# DRV8825_SHIELD_V3.net
KiCad netlist of a schematic drawn in EAGLE
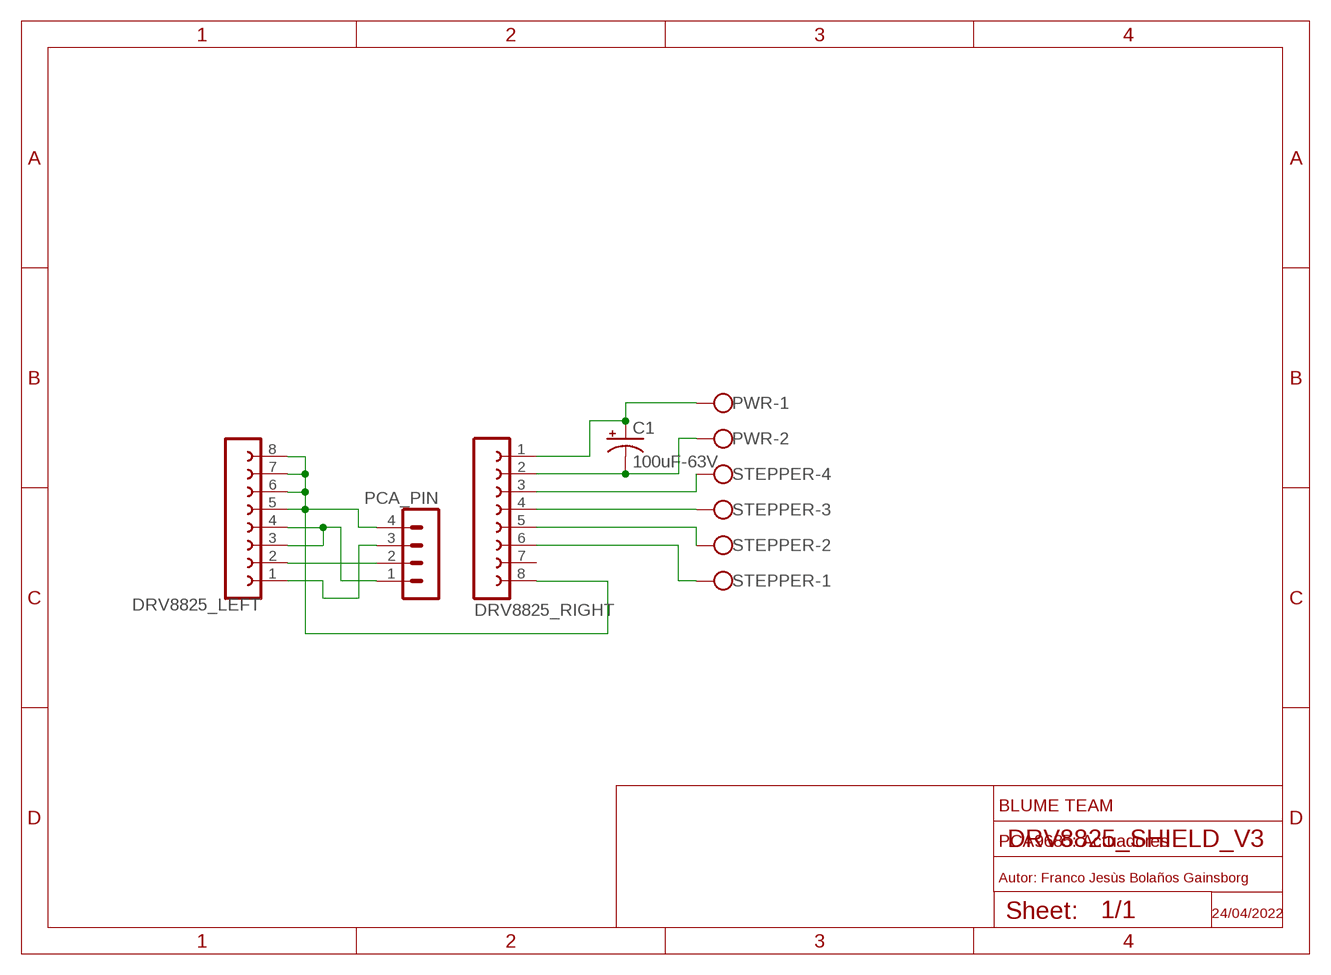
[diagram p0: schematic, sheet 1]

(export (version "E")
  (design (tool "Eeschema 10.0.6"))
  (components
    (comp (ref "C1")
      (value "100uF-63V")
      (footprint "eagle-import:E5-10,5")
      (libsource (lib "eagle-import") (part "CPOL-USE5-10.5"))
    )
    (comp (ref "DRV8825_LEFT")
      (value "FE08-1")
      (footprint "eagle-import:FE08")
      (libsource (lib "eagle-import") (part "FE08-1"))
    )
    (comp (ref "DRV8825_RIGHT")
      (value "FE08-1")
      (footprint "eagle-import:FE08")
      (libsource (lib "eagle-import") (part "FE08-1"))
    )
    (comp (ref "PCA_PIN")
      (value "MA04-1")
      (footprint "eagle-import:MA04-1")
      (libsource (lib "eagle-import") (part "MA04-1"))
    )
    (comp (ref "PWR")
      (value "W237-102")
      (footprint "eagle-import:W237-102")
      (fields (field (name "MPN") "237-102"))
      (libsource (lib "eagle-import") (part "W237-102"))
    )
    (comp (ref "STEPPER")
      (value "W237-4")
      (footprint "eagle-import:W237-4")
      (libsource (lib "eagle-import") (part "W237-4"))
    )
  )
  (nets
    (net (code "1") (name "Net-(DRV8825_LEFT-Pad1)") (class "Default")
      (node (ref "DRV8825_LEFT") (pin "1") (pinfunction "1_1") (pintype "passive"))
      (node (ref "PCA_PIN") (pin "3") (pinfunction "3_3") (pintype "passive"))
    )
    (net (code "2") (name "Net-(DRV8825_LEFT-Pad2)") (class "Default")
      (node (ref "DRV8825_LEFT") (pin "2") (pinfunction "2_2") (pintype "passive"))
      (node (ref "PCA_PIN") (pin "2") (pinfunction "2_2") (pintype "passive"))
    )
    (net (code "3") (name "Net-(DRV8825_LEFT-Pad3)") (class "Default")
      (node (ref "DRV8825_LEFT") (pin "3") (pinfunction "3_3") (pintype "passive"))
      (node (ref "DRV8825_LEFT") (pin "4") (pinfunction "4_4") (pintype "passive"))
      (node (ref "PCA_PIN") (pin "1") (pinfunction "1_1") (pintype "passive"))
    )
    (net (code "4") (name "Net-(DRV8825_LEFT-Pad5)") (class "Default")
      (node (ref "DRV8825_LEFT") (pin "5") (pinfunction "5_5") (pintype "passive"))
      (node (ref "DRV8825_LEFT") (pin "6") (pinfunction "6_6") (pintype "passive"))
      (node (ref "DRV8825_LEFT") (pin "7") (pinfunction "7_7") (pintype "passive"))
      (node (ref "DRV8825_LEFT") (pin "8") (pinfunction "8_8") (pintype "passive"))
      (node (ref "DRV8825_RIGHT") (pin "8") (pinfunction "8_8") (pintype "passive"))
      (node (ref "PCA_PIN") (pin "4") (pinfunction "4_4") (pintype "passive"))
    )
    (net (code "5") (name "Net-(PWRA-KL)") (class "Default")
      (node (ref "C1") (pin "+") (pinfunction "+_+") (pintype "passive"))
      (node (ref "DRV8825_RIGHT") (pin "1") (pinfunction "1_1") (pintype "passive"))
      (node (ref "PWR") (pin "1") (pinfunction "KL_1") (pintype "passive"))
    )
    (net (code "6") (name "Net-(PWRB-KL)") (class "Default")
      (node (ref "C1") (pin "-") (pinfunction "-_-") (pintype "passive"))
      (node (ref "DRV8825_RIGHT") (pin "2") (pinfunction "2_2") (pintype "passive"))
      (node (ref "PWR") (pin "2") (pinfunction "KL_2") (pintype "passive"))
    )
    (net (code "7") (name "Net-(STEPPERA-KL)") (class "Default")
      (node (ref "DRV8825_RIGHT") (pin "6") (pinfunction "6_6") (pintype "passive"))
      (node (ref "STEPPER") (pin "1") (pinfunction "KL_1") (pintype "passive"))
    )
    (net (code "8") (name "Net-(STEPPERB-KL)") (class "Default")
      (node (ref "DRV8825_RIGHT") (pin "5") (pinfunction "5_5") (pintype "passive"))
      (node (ref "STEPPER") (pin "2") (pinfunction "KL_2") (pintype "passive"))
    )
    (net (code "9") (name "Net-(STEPPERC-KL)") (class "Default")
      (node (ref "DRV8825_RIGHT") (pin "4") (pinfunction "4_4") (pintype "passive"))
      (node (ref "STEPPER") (pin "3") (pinfunction "KL_3") (pintype "passive"))
    )
    (net (code "10") (name "Net-(STEPPERD-KL)") (class "Default")
      (node (ref "DRV8825_RIGHT") (pin "3") (pinfunction "3_3") (pintype "passive"))
      (node (ref "STEPPER") (pin "4") (pinfunction "KL_4") (pintype "passive"))
    )
    (net (code "11") (name "unconnected-(DRV8825_RIGHT-Pad7)") (class "Default")
      (node (ref "DRV8825_RIGHT") (pin "7") (pinfunction "7_7") (pintype "passive"))
    )
  )
)
